# X7A15T-Prog.net
KiCad netlist of a schematic drawn in Altium Designer
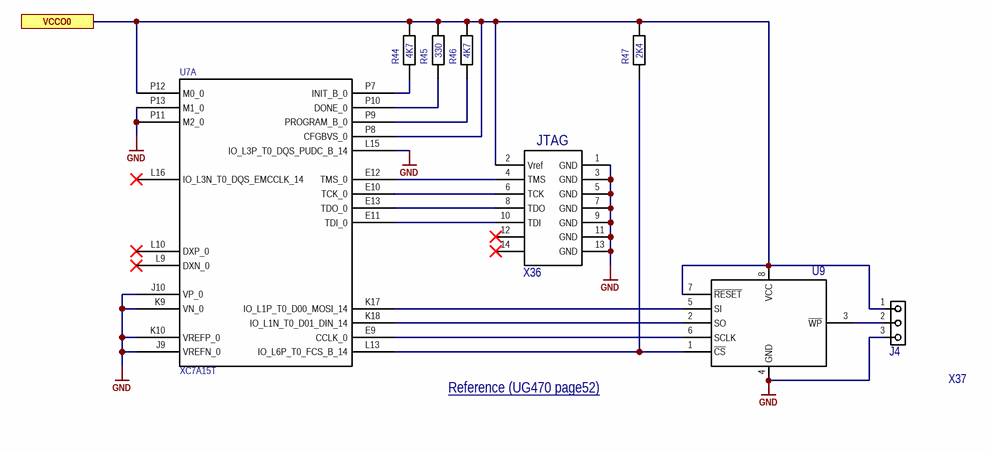
[diagram p0: X7A15T-Prog.SchDoc]

(export (version "E")
  (design (tool "Eeschema 10.0.6"))
  (components
    (comp (ref "J4")
      (value "J")
      (footprint "Header 100mil 3x1")
      (description "CONN HEADER VERT 3POS 2.54MM")
      (fields
        (field (name "02. DISTRIBUTOR PART NUMBER") "HMTSW-103-07-G-S-240")
        (field (name "13. CREATED DATE/NAME") "AUG2018/Hören")
      )
      (libsource (lib "chickenfood") (part "Header 3Pins 100mil"))
    )
    (comp (ref "R44")
      (value "4K7")
      (footprint "R0402 Reflow")
      (description "RES SMD 4.7K OHM 1% 1/16W 0402")
      (fields
        (field (name "TOLERANCE") "±1%")
        (field (name "02. DISTRIBUTOR PART NUMBER") "311-4.7KLRDKR-ND")
        (field (name "13. CREATED DATE/NAME") "AUG2018/Hören")
      )
      (libsource (lib "chickenfood") (part "R"))
    )
    (comp (ref "R45")
      (value "330")
      (footprint "R0402 Reflow")
      (description "RES SMD 330 OHM 1% 1/16W 0402")
      (fields
        (field (name "TOLERANCE") "±1%")
        (field (name "02. DISTRIBUTOR PART NUMBER") "311-330LRDKR-ND")
        (field (name "13. CREATED DATE/NAME") "AUG2018/Hören")
      )
      (libsource (lib "chickenfood") (part "R"))
    )
    (comp (ref "R46")
      (value "4K7")
      (footprint "R0402 Reflow")
      (description "RES SMD 4.7K OHM 1% 1/16W 0402")
      (fields
        (field (name "TOLERANCE") "±1%")
        (field (name "02. DISTRIBUTOR PART NUMBER") "311-4.7KLRDKR-ND")
        (field (name "13. CREATED DATE/NAME") "AUG2018/Hören")
      )
      (libsource (lib "chickenfood") (part "R"))
    )
    (comp (ref "R47")
      (value "2K4")
      (footprint "R0402 Reflow")
      (description "RES SMD 2.4K OHM 1% 1/16W 0402")
      (fields
        (field (name "TOLERANCE") "±1%")
        (field (name "02. DISTRIBUTOR PART NUMBER") "311-2.40KLRDKR-ND")
        (field (name "13. CREATED DATE/NAME") "AUG2018/Hören")
      )
      (libsource (lib "chickenfood") (part "R"))
    )
    (comp (ref "U7")
      (value "U")
      (footprint "XC7A15T-1CSG324C")
      (description "XC7A15T-1CSG324C")
      (fields (field (name "MFR") "XILINX") (field (name "NICNAME") "XC7A15T"))
      (libsource (lib "tom") (part "XC7A15T-CS324"))
    )
    (comp (ref "U9")
      (value "U")
      (footprint "SOIC8 (R-8)")
      (description "IC FLASH 32M SPI 80MHZ 8SOP")
      (fields (field (name "13. CREATED DATE/NAME") "AUG 2018 / Hören"))
      (libsource (lib "tom") (part "MX25R3235FM1IH0"))
    )
    (comp (ref "X36")
      (value "X")
      (footprint "LTMM-107-02-F-D")
      (description "CONN HEADER VERT 14POS 2MM")
      (fields
        (field (name "02. DISTRIBUTOR PART NUMBER") "LTMM-107-02-F-D-ND")
        (field (name "07. MANUFACTURER  PART NUMBER") "LTMM-107-02-F-D")
        (field (name "NICKNAME") "JTAG")
        (field (name "13. CREATED DATE/NAME") "??? / Hören")
      )
      (libsource (lib "Connectors") (part "LTMM-107-02-F-D"))
    )
    (comp (ref "X37")
      (value "X")
      (description "CONN JUMPER SHORTING .100\" GOLD")
      (fields
        (field (name "02. DISTRIBUTOR PART NUMBER") "S9337-ND")
        (field (name "07. MANUFACTURER  PART NUMBER") "QPC02SXGN-RC")
        (field (name "13. CREATED DATE/NAME") "AUG2018/Hören")
      )
      (libsource (lib "chickenfood") (part "Jumper"))
    )
  )
  (nets
    (net (code "1") (name "/VCCO0") (class "Default")
      (node (ref "J4") (pin "1") (pinfunction "1_1") (pintype "passive"))
      (node (ref "R44") (pin "2") (pinfunction "2_2") (pintype "passive"))
      (node (ref "R45") (pin "2") (pinfunction "2_2") (pintype "passive"))
      (node (ref "R46") (pin "2") (pinfunction "2_2") (pintype "passive"))
      (node (ref "R47") (pin "2") (pinfunction "2_2") (pintype "passive"))
      (node (ref "U7") (pin "P12") (pinfunction "M0_0_P12") (pintype "passive"))
      (node (ref "U7") (pin "P8") (pinfunction "CFGBVS_0_P8") (pintype "passive"))
      (node (ref "U9") (pin "7") (pinfunction "RESET_7") (pintype "passive"))
      (node (ref "U9") (pin "8") (pinfunction "VCC_8") (pintype "passive"))
      (node (ref "X36") (pin "2") (pinfunction "Vref_2") (pintype "passive"))
    )
    (net (code "2") (name "GND") (class "Default")
      (node (ref "J4") (pin "3") (pinfunction "3_3") (pintype "passive"))
      (node (ref "U7") (pin "J10") (pinfunction "VP_0_J10") (pintype "passive"))
      (node (ref "U7") (pin "J9") (pinfunction "VREFN_0_J9") (pintype "passive"))
      (node (ref "U7") (pin "K10") (pinfunction "VREFP_0_K10") (pintype "passive"))
      (node (ref "U7") (pin "K9") (pinfunction "VN_0_K9") (pintype "passive"))
      (node (ref "U7") (pin "L15") (pinfunction "IO_L3P_T0_DQS_PUDC_B_14_L15") (pintype "passive"))
      (node (ref "U7") (pin "P11") (pinfunction "M2_0_P11") (pintype "passive"))
      (node (ref "U7") (pin "P13") (pinfunction "M1_0_P13") (pintype "passive"))
      (node (ref "U9") (pin "4") (pinfunction "GND_4") (pintype "passive"))
      (node (ref "X36") (pin "1") (pinfunction "GND_1") (pintype "passive"))
      (node (ref "X36") (pin "11") (pinfunction "GND_11") (pintype "passive"))
      (node (ref "X36") (pin "13") (pinfunction "GND_13") (pintype "passive"))
      (node (ref "X36") (pin "3") (pinfunction "GND_3") (pintype "passive"))
      (node (ref "X36") (pin "5") (pinfunction "GND_5") (pintype "passive"))
      (node (ref "X36") (pin "7") (pinfunction "GND_7") (pintype "passive"))
      (node (ref "X36") (pin "9") (pinfunction "GND_9") (pintype "passive"))
    )
    (net (code "3") (name "Net-(U7A-CCLK_0)") (class "Default")
      (node (ref "U7") (pin "E9") (pinfunction "CCLK_0_E9") (pintype "passive"))
      (node (ref "U9") (pin "6") (pinfunction "SCLK_6") (pintype "passive"))
    )
    (net (code "4") (name "Net-(U7A-DONE_0)") (class "Default")
      (node (ref "R45") (pin "1") (pinfunction "1_1") (pintype "passive"))
      (node (ref "U7") (pin "P10") (pinfunction "DONE_0_P10") (pintype "passive"))
    )
    (net (code "5") (name "Net-(U7A-INIT_B_0)") (class "Default")
      (node (ref "R44") (pin "1") (pinfunction "1_1") (pintype "passive"))
      (node (ref "U7") (pin "P7") (pinfunction "INIT_B_0_P7") (pintype "passive"))
    )
    (net (code "6") (name "Net-(U7A-IO_L1N_T0_D01_DIN_14)") (class "Default")
      (node (ref "U7") (pin "K18") (pinfunction "IO_L1N_T0_D01_DIN_14_K18") (pintype "passive"))
      (node (ref "U9") (pin "2") (pinfunction "SO_2") (pintype "passive"))
    )
    (net (code "7") (name "Net-(U7A-IO_L1P_T0_D00_MOSI_14)") (class "Default")
      (node (ref "U7") (pin "K17") (pinfunction "IO_L1P_T0_D00_MOSI_14_K17") (pintype "passive"))
      (node (ref "U9") (pin "5") (pinfunction "SI_5") (pintype "passive"))
    )
    (net (code "8") (name "Net-(U7A-IO_L6P_T0_FCS_B_14)") (class "Default")
      (node (ref "R47") (pin "1") (pinfunction "1_1") (pintype "passive"))
      (node (ref "U7") (pin "L13") (pinfunction "IO_L6P_T0_FCS_B_14_L13") (pintype "passive"))
      (node (ref "U9") (pin "1") (pinfunction "CS_1") (pintype "passive"))
    )
    (net (code "9") (name "Net-(U7A-PROGRAM_B_0)") (class "Default")
      (node (ref "R46") (pin "1") (pinfunction "1_1") (pintype "passive"))
      (node (ref "U7") (pin "P9") (pinfunction "PROGRAM_B_0_P9") (pintype "passive"))
    )
    (net (code "10") (name "Net-(U7A-TCK_0)") (class "Default")
      (node (ref "U7") (pin "E10") (pinfunction "TCK_0_E10") (pintype "passive"))
      (node (ref "X36") (pin "6") (pinfunction "TCK_6") (pintype "passive"))
    )
    (net (code "11") (name "Net-(U7A-TDI_0)") (class "Default")
      (node (ref "U7") (pin "E11") (pinfunction "TDI_0_E11") (pintype "passive"))
      (node (ref "X36") (pin "10") (pinfunction "TDI_10") (pintype "passive"))
    )
    (net (code "12") (name "Net-(U7A-TDO_0)") (class "Default")
      (node (ref "U7") (pin "E13") (pinfunction "TDO_0_E13") (pintype "passive"))
      (node (ref "X36") (pin "8") (pinfunction "TDO_8") (pintype "passive"))
    )
    (net (code "13") (name "Net-(U7A-TMS_0)") (class "Default")
      (node (ref "U7") (pin "E12") (pinfunction "TMS_0_E12") (pintype "passive"))
      (node (ref "X36") (pin "4") (pinfunction "TMS_4") (pintype "passive"))
    )
    (net (code "14") (name "Net-(U9-WP)") (class "Default")
      (node (ref "J4") (pin "2") (pinfunction "2_2") (pintype "passive"))
      (node (ref "U9") (pin "3") (pinfunction "WP_3") (pintype "passive"))
    )
    (net (code "15") (name "unconnected-(U7A-DXN_0-PadL9)") (class "Default")
      (node (ref "U7") (pin "L9") (pinfunction "DXN_0_L9") (pintype "passive+no_connect"))
    )
    (net (code "16") (name "unconnected-(U7A-DXP_0-PadL10)") (class "Default")
      (node (ref "U7") (pin "L10") (pinfunction "DXP_0_L10") (pintype "passive+no_connect"))
    )
    (net (code "17") (name "unconnected-(U7A-IO_L3N_T0_DQS_EMCCLK_14-PadL16)") (class "Default")
      (node (ref "U7") (pin "L16") (pinfunction "IO_L3N_T0_DQS_EMCCLK_14_L16") (pintype "passive+no_connect"))
    )
    (net (code "18") (name "unconnected-(X36-Pad12)") (class "Default")
      (node (ref "X36") (pin "12") (pinfunction "12_12") (pintype "passive+no_connect"))
    )
    (net (code "19") (name "unconnected-(X36-Pad14)") (class "Default")
      (node (ref "X36") (pin "14") (pinfunction "14_14") (pintype "passive+no_connect"))
    )
  )
)
